# data_proV2_0_-_B.net
KiCad netlist of a schematic drawn in EAGLE
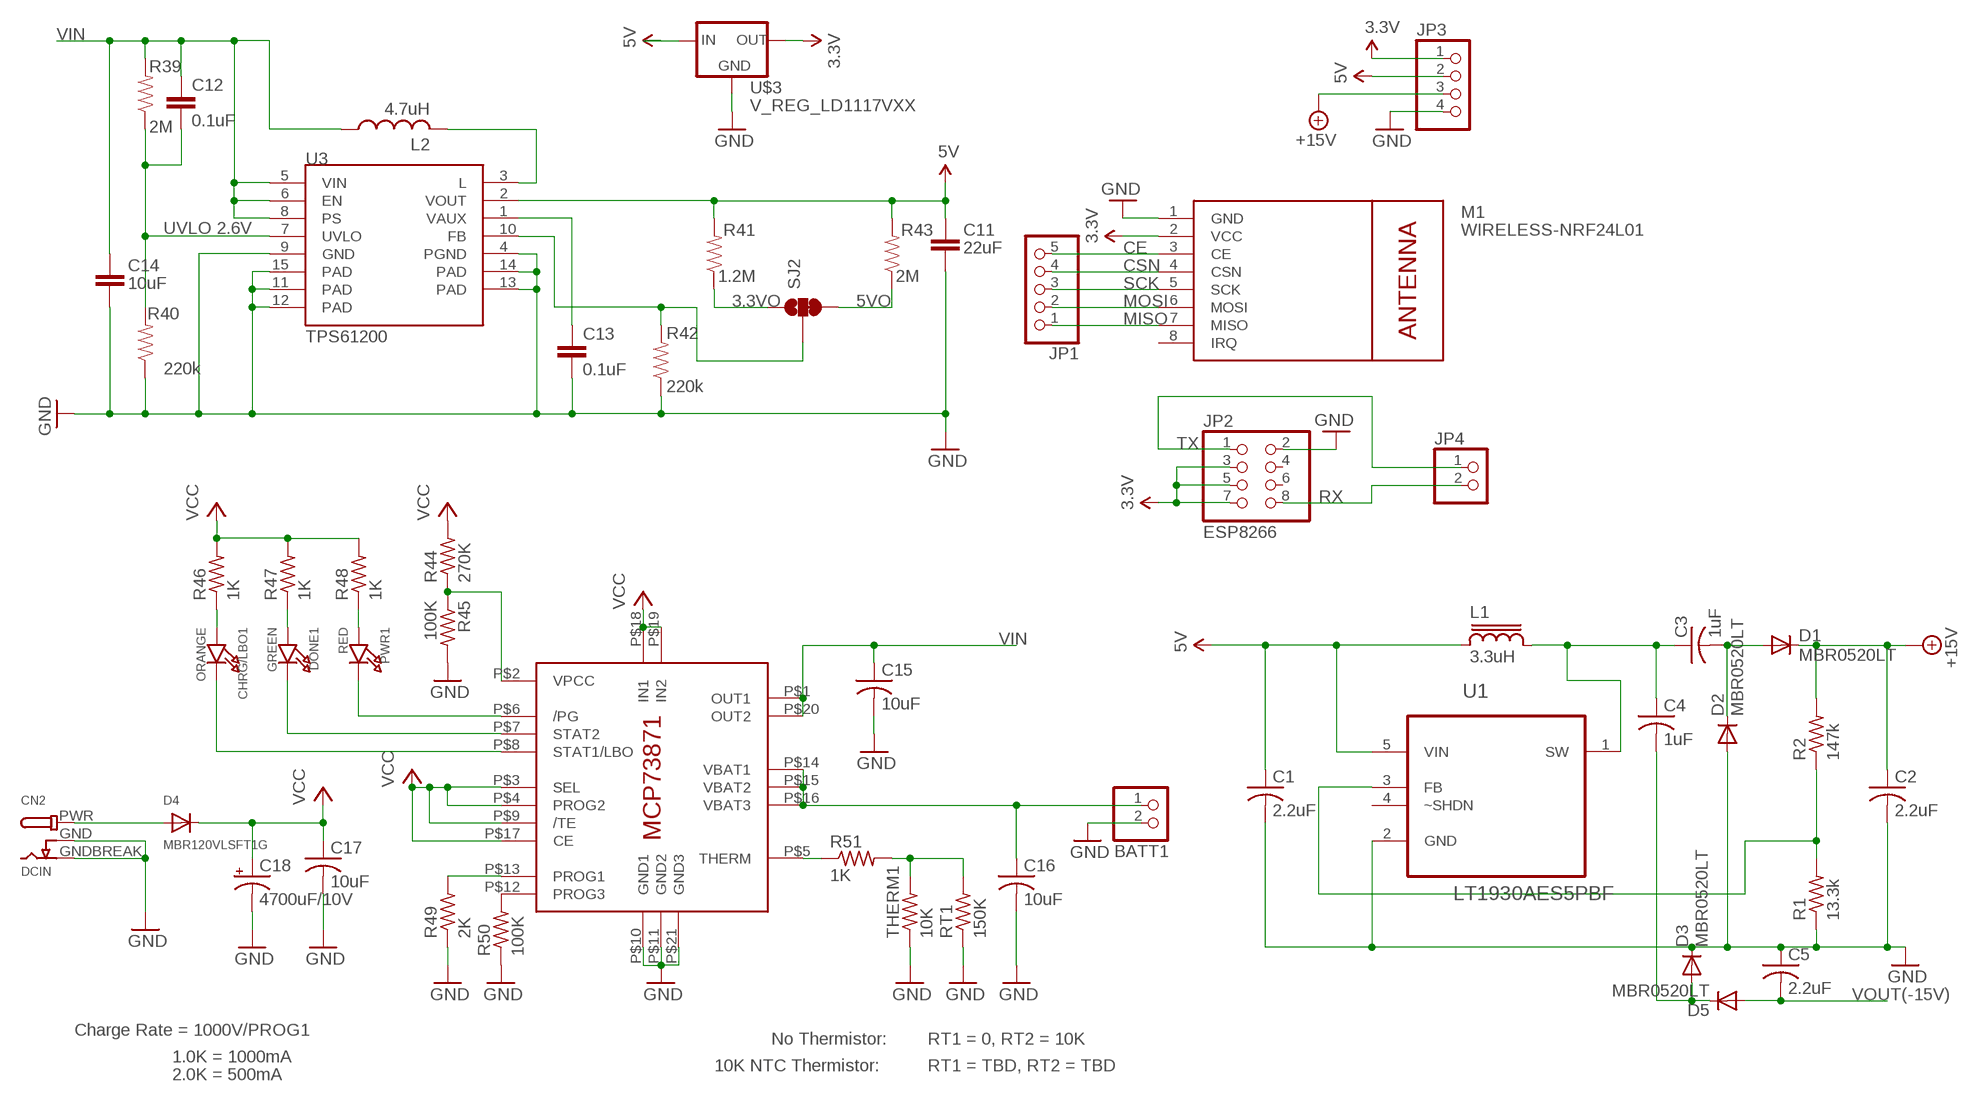
[diagram p0: schematic, sheet 1]

(export (version "E")
  (design (tool "Eeschema 10.0.6"))
  (components
    (comp (ref "BATT1")
      (value "JST_2PIN-SMT-RA")
      (footprint "eagle-import:JST-PH-2-SMT-RA")
      (libsource (lib "eagle-import") (part "JST_2PIN-SMT-RA"))
    )
    (comp (ref "C1")
      (value "2.2uF")
      (footprint "eagle-import:C0805")
      (libsource (lib "eagle-import") (part "C-USC0805"))
    )
    (comp (ref "C2")
      (value "2.2uF")
      (footprint "eagle-import:C1206")
      (libsource (lib "eagle-import") (part "rcl_C-USC1206"))
    )
    (comp (ref "C3")
      (value "1uF")
      (footprint "eagle-import:C1206")
      (libsource (lib "eagle-import") (part "rcl_C-USC1206"))
    )
    (comp (ref "C4")
      (value "1uF")
      (footprint "eagle-import:C1206")
      (libsource (lib "eagle-import") (part "rcl_C-USC1206"))
    )
    (comp (ref "C5")
      (value "2.2uF")
      (footprint "eagle-import:C1206")
      (libsource (lib "eagle-import") (part "rcl_C-USC1206"))
    )
    (comp (ref "C11")
      (value "22uF")
      (footprint "eagle-import:0805")
      (libsource (lib "eagle-import") (part "CAP0805"))
    )
    (comp (ref "C12")
      (value "0.1uF")
      (footprint "eagle-import:0603-CAP")
      (libsource (lib "eagle-import") (part "CAP0603-CAP"))
    )
    (comp (ref "C13")
      (value "0.1uF")
      (footprint "eagle-import:0603-CAP")
      (libsource (lib "eagle-import") (part "CAP0603-CAP"))
    )
    (comp (ref "C14")
      (value "10uF")
      (footprint "eagle-import:1206")
      (libsource (lib "eagle-import") (part "CAP1206"))
    )
    (comp (ref "C15")
      (value "10uF")
      (footprint "eagle-import:C0805K")
      (libsource (lib "eagle-import") (part "C-USC0805K"))
    )
    (comp (ref "C16")
      (value "10uF")
      (footprint "eagle-import:C0805K")
      (libsource (lib "eagle-import") (part "C-USC0805K"))
    )
    (comp (ref "C17")
      (value "10uF")
      (footprint "eagle-import:C0805K")
      (libsource (lib "eagle-import") (part "C-USC0805K"))
    )
    (comp (ref "C18")
      (value "4700uF/10V")
      (footprint "eagle-import:E5-13")
      (libsource (lib "eagle-import") (part "CPOL-USE5-13"))
    )
    (comp (ref "CHRG/LBO1")
      (value "ORANGE")
      (footprint "eagle-import:CHIPLED_0805_NOOUTLINE")
      (libsource (lib "eagle-import") (part "LED0805_NOOUTLINE"))
    )
    (comp (ref "CN2")
      (value "DCIN")
      (footprint "eagle-import:DCJACK_2MM_SMT")
      (libsource (lib "eagle-import") (part "DCBARRELSMT"))
    )
    (comp (ref "D1")
      (value "MBR0520LT")
      (footprint "eagle-import:SOD123")
      (libsource (lib "eagle-import") (part "MBR0520LT"))
    )
    (comp (ref "D2")
      (value "MBR0520LT")
      (footprint "eagle-import:SOD123")
      (libsource (lib "eagle-import") (part "MBR0520LT"))
    )
    (comp (ref "D3")
      (value "MBR0520LT")
      (footprint "eagle-import:SOD123")
      (libsource (lib "eagle-import") (part "MBR0520LT"))
    )
    (comp (ref "D4")
      (value "MBR120VLSFT1G")
      (footprint "eagle-import:SOD-123")
      (libsource (lib "eagle-import") (part "DIODESOD-123"))
    )
    (comp (ref "D5")
      (value "MBR0520LT")
      (footprint "eagle-import:SOD123")
      (libsource (lib "eagle-import") (part "MBR0520LT"))
    )
    (comp (ref "DONE1")
      (value "GREEN")
      (footprint "eagle-import:CHIPLED_0805_NOOUTLINE")
      (libsource (lib "eagle-import") (part "LED0805_NOOUTLINE"))
    )
    (comp (ref "IC8")
      (value "MCP73871")
      (footprint "eagle-import:QFN20_4MM")
      (libsource (lib "eagle-import") (part "MCP73871"))
    )
    (comp (ref "JP1")
      (value "PINHD-1X5")
      (footprint "eagle-import:1X05")
      (libsource (lib "eagle-import") (part "PINHD-1X5"))
    )
    (comp (ref "JP2")
      (value "ESP8266")
      (footprint "eagle-import:2X04")
      (libsource (lib "eagle-import") (part "PINHD-2X4"))
    )
    (comp (ref "JP3")
      (value "PINHD-1X4")
      (footprint "eagle-import:1X04")
      (libsource (lib "eagle-import") (part "PINHD-1X4"))
    )
    (comp (ref "JP4")
      (value "PINHD-1X2")
      (footprint "eagle-import:1X02")
      (libsource (lib "eagle-import") (part "PINHD-1X2"))
    )
    (comp (ref "L1")
      (value "3.3uH")
      (footprint "eagle-import:CR43")
      (libsource (lib "eagle-import") (part "CR43"))
    )
    (comp (ref "L2")
      (value "4.7uH")
      (footprint "eagle-import:L3225M")
      (libsource (lib "eagle-import") (part "L-USL3225M"))
    )
    (comp (ref "M1")
      (value "WIRELESS-NRF24L01")
      (footprint "eagle-import:WIRELESS-NRF24L01")
      (libsource (lib "eagle-import") (part "WIRELESS-NRF24L01"))
    )
    (comp (ref "PWR1")
      (value "RED")
      (footprint "eagle-import:CHIPLED_0805_NOOUTLINE")
      (libsource (lib "eagle-import") (part "LED0805_NOOUTLINE"))
    )
    (comp (ref "R1")
      (value "13.3k")
      (footprint "eagle-import:R0805")
      (libsource (lib "eagle-import") (part "rcl_R-US_R0805"))
    )
    (comp (ref "R2")
      (value "147k")
      (footprint "eagle-import:R0805")
      (libsource (lib "eagle-import") (part "rcl_R-US_R0805"))
    )
    (comp (ref "R39")
      (value "2M")
      (footprint "eagle-import:0603-RES")
      (libsource (lib "eagle-import") (part "RESISTOR0603-RES"))
    )
    (comp (ref "R40")
      (value "220k")
      (footprint "eagle-import:0603-RES")
      (libsource (lib "eagle-import") (part "RESISTOR0603-RES"))
    )
    (comp (ref "R41")
      (value "1.2M")
      (footprint "eagle-import:0603-RES")
      (libsource (lib "eagle-import") (part "RESISTOR0603-RES"))
    )
    (comp (ref "R42")
      (value "220k")
      (footprint "eagle-import:0603-RES")
      (libsource (lib "eagle-import") (part "RESISTOR0603-RES"))
    )
    (comp (ref "R43")
      (value "2M")
      (footprint "eagle-import:0603-RES")
      (libsource (lib "eagle-import") (part "RESISTOR0603-RES"))
    )
    (comp (ref "R44")
      (value "270K")
      (footprint "eagle-import:R0805")
      (libsource (lib "eagle-import") (part "R-US_R0805"))
    )
    (comp (ref "R45")
      (value "100K")
      (footprint "eagle-import:R0805")
      (libsource (lib "eagle-import") (part "R-US_R0805"))
    )
    (comp (ref "R46")
      (value "1K")
      (footprint "eagle-import:R0805")
      (libsource (lib "eagle-import") (part "R-US_R0805"))
    )
    (comp (ref "R47")
      (value "1K")
      (footprint "eagle-import:R0805")
      (libsource (lib "eagle-import") (part "R-US_R0805"))
    )
    (comp (ref "R48")
      (value "1K")
      (footprint "eagle-import:R0805")
      (libsource (lib "eagle-import") (part "R-US_R0805"))
    )
    (comp (ref "R49")
      (value "2K")
      (footprint "eagle-import:0805-THM")
      (libsource (lib "eagle-import") (part "R-US_FLIPFLOP"))
    )
    (comp (ref "R50")
      (value "100K")
      (footprint "eagle-import:R0805")
      (libsource (lib "eagle-import") (part "R-US_R0805"))
    )
    (comp (ref "R51")
      (value "1K")
      (footprint "eagle-import:M0805")
      (libsource (lib "eagle-import") (part "R-US_M0805"))
    )
    (comp (ref "RT1")
      (value "150K")
      (footprint "eagle-import:M0805")
      (libsource (lib "eagle-import") (part "R-US_M0805"))
    )
    (comp (ref "SJ2")
      (value "SOLDERJUMPER_2WAYPASTE2&3")
      (footprint "eagle-import:SJ_3_PASTE2&3")
      (libsource (lib "eagle-import") (part "SOLDERJUMPER_2WAYPASTE2&3"))
    )
    (comp (ref "THERM1")
      (value "10K")
      (footprint "eagle-import:0805-THM")
      (libsource (lib "eagle-import") (part "R-US_FLIPFLOP"))
    )
    (comp (ref "U$3")
      (value "V_REG_LD1117VXX")
      (footprint "eagle-import:78XXL")
      (libsource (lib "eagle-import") (part "V_REG_LD1117VXX"))
    )
    (comp (ref "U1")
      (value "LT1930AES5PBF")
      (footprint "eagle-import:SOT95P280X145-5N")
      (fields (field (name "MPN") "LT1930AES5#PBF"))
      (libsource (lib "eagle-import") (part "LT1930AES5PBF"))
    )
    (comp (ref "U3")
      (value "TPS61200")
      (footprint "eagle-import:QFN-10_PAD")
      (libsource (lib "eagle-import") (part "TPS61200"))
    )
  )
  (nets
    (net (code "1") (name "+15V") (class "Default")
      (node (ref "C2") (pin "1") (pinfunction "1_1") (pintype "passive"))
      (node (ref "D1") (pin "C") (pinfunction "C_C") (pintype "passive"))
      (node (ref "JP3") (pin "3") (pinfunction "3_3") (pintype "passive"))
      (node (ref "R2") (pin "2") (pinfunction "2_2") (pintype "passive"))
    )
    (net (code "2") (name "/3.3VO") (class "Default")
      (node (ref "R41") (pin "1") (pinfunction "1_1") (pintype "passive"))
      (node (ref "SJ2") (pin "1") (pinfunction "1_1") (pintype "passive"))
    )
    (net (code "3") (name "/5VO") (class "Default")
      (node (ref "R43") (pin "1") (pinfunction "1_1") (pintype "passive"))
      (node (ref "SJ2") (pin "3") (pinfunction "3_3") (pintype "passive"))
    )
    (net (code "4") (name "/CE") (class "Default")
      (node (ref "JP1") (pin "5") (pinfunction "5_5") (pintype "passive"))
      (node (ref "M1") (pin "3") (pinfunction "CE_3") (pintype "bidirectional"))
    )
    (net (code "5") (name "/CSN") (class "Default")
      (node (ref "JP1") (pin "4") (pinfunction "4_4") (pintype "passive"))
      (node (ref "M1") (pin "4") (pinfunction "CSN_4") (pintype "bidirectional"))
    )
    (net (code "6") (name "/MISO") (class "Default")
      (node (ref "JP1") (pin "1") (pinfunction "1_1") (pintype "passive"))
      (node (ref "M1") (pin "7") (pinfunction "MISO_7") (pintype "bidirectional"))
    )
    (net (code "7") (name "/MOSI") (class "Default")
      (node (ref "JP1") (pin "2") (pinfunction "2_2") (pintype "passive"))
      (node (ref "M1") (pin "6") (pinfunction "MOSI_6") (pintype "bidirectional"))
    )
    (net (code "8") (name "/RX") (class "Default")
      (node (ref "JP2") (pin "8") (pinfunction "8_8") (pintype "passive"))
      (node (ref "JP4") (pin "2") (pinfunction "2_2") (pintype "passive"))
    )
    (net (code "9") (name "/SCK") (class "Default")
      (node (ref "JP1") (pin "3") (pinfunction "3_3") (pintype "passive"))
      (node (ref "M1") (pin "5") (pinfunction "SCK_5") (pintype "bidirectional"))
    )
    (net (code "10") (name "/TX") (class "Default")
      (node (ref "JP2") (pin "1") (pinfunction "1_1") (pintype "passive"))
      (node (ref "JP4") (pin "1") (pinfunction "1_1") (pintype "passive"))
    )
    (net (code "11") (name "/VIN") (class "Default")
      (node (ref "C12") (pin "1") (pinfunction "1_1") (pintype "passive"))
      (node (ref "C14") (pin "1") (pinfunction "1_1") (pintype "passive"))
      (node (ref "C15") (pin "1") (pinfunction "1_1") (pintype "passive"))
      (node (ref "IC8") (pin "P$1") (pinfunction "OUT1_P$1") (pintype "output"))
      (node (ref "IC8") (pin "P$20") (pinfunction "OUT2_P$20") (pintype "output"))
      (node (ref "L2") (pin "1") (pinfunction "1_1") (pintype "passive"))
      (node (ref "R39") (pin "2") (pinfunction "2_2") (pintype "passive"))
      (node (ref "U3") (pin "5") (pinfunction "VIN_5") (pintype "power_in"))
      (node (ref "U3") (pin "6") (pinfunction "EN_6") (pintype "input"))
      (node (ref "U3") (pin "8") (pinfunction "PS_8") (pintype "input"))
    )
    (net (code "12") (name "/VOUT(-15V)") (class "Default")
      (node (ref "C5") (pin "2") (pinfunction "2_2") (pintype "passive"))
      (node (ref "D5") (pin "A") (pinfunction "A_A") (pintype "passive"))
    )
    (net (code "13") (name "3.3V") (class "Default")
      (node (ref "JP2") (pin "3") (pinfunction "3_3") (pintype "passive"))
      (node (ref "JP2") (pin "5") (pinfunction "5_5") (pintype "passive"))
      (node (ref "JP2") (pin "7") (pinfunction "7_7") (pintype "passive"))
      (node (ref "JP3") (pin "1") (pinfunction "1_1") (pintype "passive"))
      (node (ref "M1") (pin "2") (pinfunction "VCC_2") (pintype "power_in"))
      (node (ref "U$3") (pin "GND") (pinfunction "OUT_GND") (pintype "passive"))
    )
    (net (code "14") (name "5V") (class "Default")
      (node (ref "C1") (pin "1") (pinfunction "1_1") (pintype "passive"))
      (node (ref "C11") (pin "1") (pinfunction "1_1") (pintype "passive"))
      (node (ref "JP3") (pin "2") (pinfunction "2_2") (pintype "passive"))
      (node (ref "L1") (pin "1") (pinfunction "1_1") (pintype "passive"))
      (node (ref "R41") (pin "2") (pinfunction "2_2") (pintype "passive"))
      (node (ref "R43") (pin "2") (pinfunction "2_2") (pintype "passive"))
      (node (ref "U$3") (pin "OUT") (pinfunction "IN_OUT") (pintype "input"))
      (node (ref "U1") (pin "5") (pinfunction "VIN_5") (pintype "power_in"))
      (node (ref "U3") (pin "2") (pinfunction "VOUT_2") (pintype "passive"))
    )
    (net (code "15") (name "GND") (class "Default")
      (node (ref "BATT1") (pin "2") (pinfunction "1_2") (pintype "passive"))
      (node (ref "C1") (pin "2") (pinfunction "2_2") (pintype "passive"))
      (node (ref "C11") (pin "2") (pinfunction "2_2") (pintype "passive"))
      (node (ref "C13") (pin "2") (pinfunction "2_2") (pintype "passive"))
      (node (ref "C14") (pin "2") (pinfunction "2_2") (pintype "passive"))
      (node (ref "C15") (pin "2") (pinfunction "2_2") (pintype "passive"))
      (node (ref "C16") (pin "2") (pinfunction "2_2") (pintype "passive"))
      (node (ref "C17") (pin "2") (pinfunction "2_2") (pintype "passive"))
      (node (ref "C18") (pin "-") (pinfunction "-_-") (pintype "passive"))
      (node (ref "C2") (pin "2") (pinfunction "2_2") (pintype "passive"))
      (node (ref "C5") (pin "1") (pinfunction "1_1") (pintype "passive"))
      (node (ref "CN2") (pin "GND") (pinfunction "GNDBREAK_GND") (pintype "power_in"))
      (node (ref "CN2") (pin "GNDBREAK") (pinfunction "GND_GNDBREAK") (pintype "power_in"))
      (node (ref "D2") (pin "A") (pinfunction "A_A") (pintype "passive"))
      (node (ref "D3") (pin "C") (pinfunction "C_C") (pintype "passive"))
      (node (ref "IC8") (pin "P$10") (pinfunction "GND1_P$10") (pintype "power_in"))
      (node (ref "IC8") (pin "P$11") (pinfunction "GND2_P$11") (pintype "power_in"))
      (node (ref "IC8") (pin "P$21") (pinfunction "GND3_P$21") (pintype "power_in"))
      (node (ref "JP2") (pin "2") (pinfunction "2_2") (pintype "passive"))
      (node (ref "JP3") (pin "4") (pinfunction "4_4") (pintype "passive"))
      (node (ref "M1") (pin "1") (pinfunction "GND_1") (pintype "power_in"))
      (node (ref "R1") (pin "1") (pinfunction "1_1") (pintype "passive"))
      (node (ref "R40") (pin "1") (pinfunction "1_1") (pintype "passive"))
      (node (ref "R42") (pin "1") (pinfunction "1_1") (pintype "passive"))
      (node (ref "R45") (pin "2") (pinfunction "2_2") (pintype "passive"))
      (node (ref "R49") (pin "1") (pinfunction "1_1") (pintype "passive"))
      (node (ref "R50") (pin "1") (pinfunction "1_1") (pintype "passive"))
      (node (ref "RT1") (pin "1") (pinfunction "1_1") (pintype "passive"))
      (node (ref "THERM1") (pin "1") (pinfunction "1_1") (pintype "passive"))
      (node (ref "U$3") (pin "IN") (pinfunction "GND_IN") (pintype "input"))
      (node (ref "U1") (pin "2") (pinfunction "GND_2") (pintype "passive"))
      (node (ref "U3") (pin "11") (pinfunction "PAD_11") (pintype "power_in"))
      (node (ref "U3") (pin "12") (pinfunction "PAD_12") (pintype "power_in"))
      (node (ref "U3") (pin "13") (pinfunction "PAD_13") (pintype "power_in"))
      (node (ref "U3") (pin "14") (pinfunction "PAD_14") (pintype "power_in"))
      (node (ref "U3") (pin "15") (pinfunction "PAD_15") (pintype "power_in"))
      (node (ref "U3") (pin "4") (pinfunction "PGND_4") (pintype "power_in"))
      (node (ref "U3") (pin "9") (pinfunction "GND_9") (pintype "power_in"))
    )
    (net (code "16") (name "Net-(BATT1-2)") (class "Default")
      (node (ref "BATT1") (pin "1") (pinfunction "2_1") (pintype "passive"))
      (node (ref "C16") (pin "1") (pinfunction "1_1") (pintype "passive"))
      (node (ref "IC8") (pin "P$14") (pinfunction "VBAT1_P$14") (pintype "output"))
      (node (ref "IC8") (pin "P$15") (pinfunction "VBAT2_P$15") (pintype "output"))
      (node (ref "IC8") (pin "P$16") (pinfunction "VBAT3_P$16") (pintype "output"))
    )
    (net (code "17") (name "Net-(C3-Pad2)") (class "Default")
      (node (ref "C3") (pin "2") (pinfunction "2_2") (pintype "passive"))
      (node (ref "D1") (pin "A") (pinfunction "A_A") (pintype "passive"))
      (node (ref "D2") (pin "C") (pinfunction "C_C") (pintype "passive"))
    )
    (net (code "18") (name "Net-(C4-Pad2)") (class "Default")
      (node (ref "C4") (pin "2") (pinfunction "2_2") (pintype "passive"))
      (node (ref "D3") (pin "A") (pinfunction "A_A") (pintype "passive"))
      (node (ref "D5") (pin "C") (pinfunction "C_C") (pintype "passive"))
    )
    (net (code "19") (name "Net-(CHRG/LBO1-PadA)") (class "Default")
      (node (ref "CHRG/LBO1") (pin "A") (pinfunction "A_A") (pintype "passive"))
      (node (ref "R46") (pin "1") (pinfunction "1_1") (pintype "passive"))
    )
    (net (code "20") (name "Net-(CN2-PadPWR)") (class "Default")
      (node (ref "CN2") (pin "PWR") (pinfunction "PWR_PWR") (pintype "power_in"))
      (node (ref "D4") (pin "A") (pinfunction "A_A") (pintype "passive"))
    )
    (net (code "21") (name "Net-(DONE1-PadA)") (class "Default")
      (node (ref "DONE1") (pin "A") (pinfunction "A_A") (pintype "passive"))
      (node (ref "R47") (pin "1") (pinfunction "1_1") (pintype "passive"))
    )
    (net (code "22") (name "Net-(IC8-PROG1)") (class "Default")
      (node (ref "IC8") (pin "P$13") (pinfunction "PROG1_P$13") (pintype "input"))
      (node (ref "R49") (pin "2") (pinfunction "2_2") (pintype "passive"))
    )
    (net (code "23") (name "Net-(IC8-PROG3)") (class "Default")
      (node (ref "IC8") (pin "P$12") (pinfunction "PROG3_P$12") (pintype "input"))
      (node (ref "R50") (pin "2") (pinfunction "2_2") (pintype "passive"))
    )
    (net (code "24") (name "Net-(IC8-STAT1{slash}LBO)") (class "Default")
      (node (ref "CHRG/LBO1") (pin "C") (pinfunction "C_C") (pintype "passive"))
      (node (ref "IC8") (pin "P$8") (pinfunction "STAT1/LBO_P$8") (pintype "output"))
    )
    (net (code "25") (name "Net-(IC8-STAT2)") (class "Default")
      (node (ref "DONE1") (pin "C") (pinfunction "C_C") (pintype "passive"))
      (node (ref "IC8") (pin "P$7") (pinfunction "STAT2_P$7") (pintype "output"))
    )
    (net (code "26") (name "Net-(IC8-THERM)") (class "Default")
      (node (ref "IC8") (pin "P$5") (pinfunction "THERM_P$5") (pintype "input"))
      (node (ref "R51") (pin "1") (pinfunction "1_1") (pintype "passive"))
    )
    (net (code "27") (name "Net-(IC8-VPCC)") (class "Default")
      (node (ref "IC8") (pin "P$2") (pinfunction "VPCC_P$2") (pintype "input"))
      (node (ref "R44") (pin "1") (pinfunction "1_1") (pintype "passive"))
      (node (ref "R45") (pin "1") (pinfunction "1_1") (pintype "passive"))
    )
    (net (code "28") (name "Net-(IC8-{slash}PG)") (class "Default")
      (node (ref "IC8") (pin "P$6") (pinfunction "/PG_P$6") (pintype "output"))
      (node (ref "PWR1") (pin "C") (pinfunction "C_C") (pintype "passive"))
    )
    (net (code "29") (name "Net-(PWR1-PadA)") (class "Default")
      (node (ref "PWR1") (pin "A") (pinfunction "A_A") (pintype "passive"))
      (node (ref "R48") (pin "1") (pinfunction "1_1") (pintype "passive"))
    )
    (net (code "30") (name "Net-(R51-Pad2)") (class "Default")
      (node (ref "R51") (pin "2") (pinfunction "2_2") (pintype "passive"))
      (node (ref "RT1") (pin "2") (pinfunction "2_2") (pintype "passive"))
      (node (ref "THERM1") (pin "2") (pinfunction "2_2") (pintype "passive"))
    )
    (net (code "31") (name "Net-(U1-FB)") (class "Default")
      (node (ref "R1") (pin "2") (pinfunction "2_2") (pintype "passive"))
      (node (ref "R2") (pin "1") (pinfunction "1_1") (pintype "passive"))
      (node (ref "U1") (pin "3") (pinfunction "FB_3") (pintype "input"))
    )
    (net (code "32") (name "Net-(U1-SW)") (class "Default")
      (node (ref "C3") (pin "1") (pinfunction "1_1") (pintype "passive"))
      (node (ref "C4") (pin "1") (pinfunction "1_1") (pintype "passive"))
      (node (ref "L1") (pin "2") (pinfunction "2_2") (pintype "passive"))
      (node (ref "U1") (pin "1") (pinfunction "SW_1") (pintype "output"))
    )
    (net (code "33") (name "Net-(U3-FB)") (class "Default")
      (node (ref "R42") (pin "2") (pinfunction "2_2") (pintype "passive"))
      (node (ref "SJ2") (pin "2") (pinfunction "2_2") (pintype "passive"))
      (node (ref "U3") (pin "10") (pinfunction "FB_10") (pintype "passive"))
    )
    (net (code "34") (name "Net-(U3-L)") (class "Default")
      (node (ref "L2") (pin "2") (pinfunction "2_2") (pintype "passive"))
      (node (ref "U3") (pin "3") (pinfunction "L_3") (pintype "passive"))
    )
    (net (code "35") (name "Net-(U3-UVLO)") (class "Default")
      (node (ref "C12") (pin "2") (pinfunction "2_2") (pintype "passive"))
      (node (ref "R39") (pin "1") (pinfunction "1_1") (pintype "passive"))
      (node (ref "R40") (pin "2") (pinfunction "2_2") (pintype "passive"))
      (node (ref "U3") (pin "7") (pinfunction "UVLO_7") (pintype "passive"))
    )
    (net (code "36") (name "Net-(U3-VAUX)") (class "Default")
      (node (ref "C13") (pin "1") (pinfunction "1_1") (pintype "passive"))
      (node (ref "U3") (pin "1") (pinfunction "VAUX_1") (pintype "passive"))
    )
    (net (code "37") (name "VCC") (class "Default")
      (node (ref "C17") (pin "1") (pinfunction "1_1") (pintype "passive"))
      (node (ref "C18") (pin "+") (pinfunction "+_+") (pintype "passive"))
      (node (ref "D4") (pin "C") (pinfunction "C_C") (pintype "passive"))
      (node (ref "IC8") (pin "P$17") (pinfunction "CE_P$17") (pintype "input"))
      (node (ref "IC8") (pin "P$18") (pinfunction "IN1_P$18") (pintype "input"))
      (node (ref "IC8") (pin "P$19") (pinfunction "IN2_P$19") (pintype "input"))
      (node (ref "IC8") (pin "P$3") (pinfunction "SEL_P$3") (pintype "input"))
      (node (ref "IC8") (pin "P$4") (pinfunction "PROG2_P$4") (pintype "input"))
      (node (ref "IC8") (pin "P$9") (pinfunction "/TE_P$9") (pintype "input"))
      (node (ref "R44") (pin "2") (pinfunction "2_2") (pintype "passive"))
      (node (ref "R46") (pin "2") (pinfunction "2_2") (pintype "passive"))
      (node (ref "R47") (pin "2") (pinfunction "2_2") (pintype "passive"))
      (node (ref "R48") (pin "2") (pinfunction "2_2") (pintype "passive"))
    )
    (net (code "38") (name "unconnected-(JP2-Pad4)") (class "Default")
      (node (ref "JP2") (pin "4") (pinfunction "4_4") (pintype "passive"))
    )
    (net (code "39") (name "unconnected-(JP2-Pad6)") (class "Default")
      (node (ref "JP2") (pin "6") (pinfunction "6_6") (pintype "passive"))
    )
    (net (code "40") (name "unconnected-(M1-IRQ-Pad8)") (class "Default")
      (node (ref "M1") (pin "8") (pinfunction "IRQ_8") (pintype "bidirectional"))
    )
    (net (code "41") (name "unconnected-(U1-~{SHDN}-Pad4)") (class "Default")
      (node (ref "U1") (pin "4") (pinfunction "~{SHDN}_4") (pintype "input"))
    )
  )
)
